# avoccado-avr-pcb-kane-a1.net
KiCad netlist of a schematic drawn in EAGLE
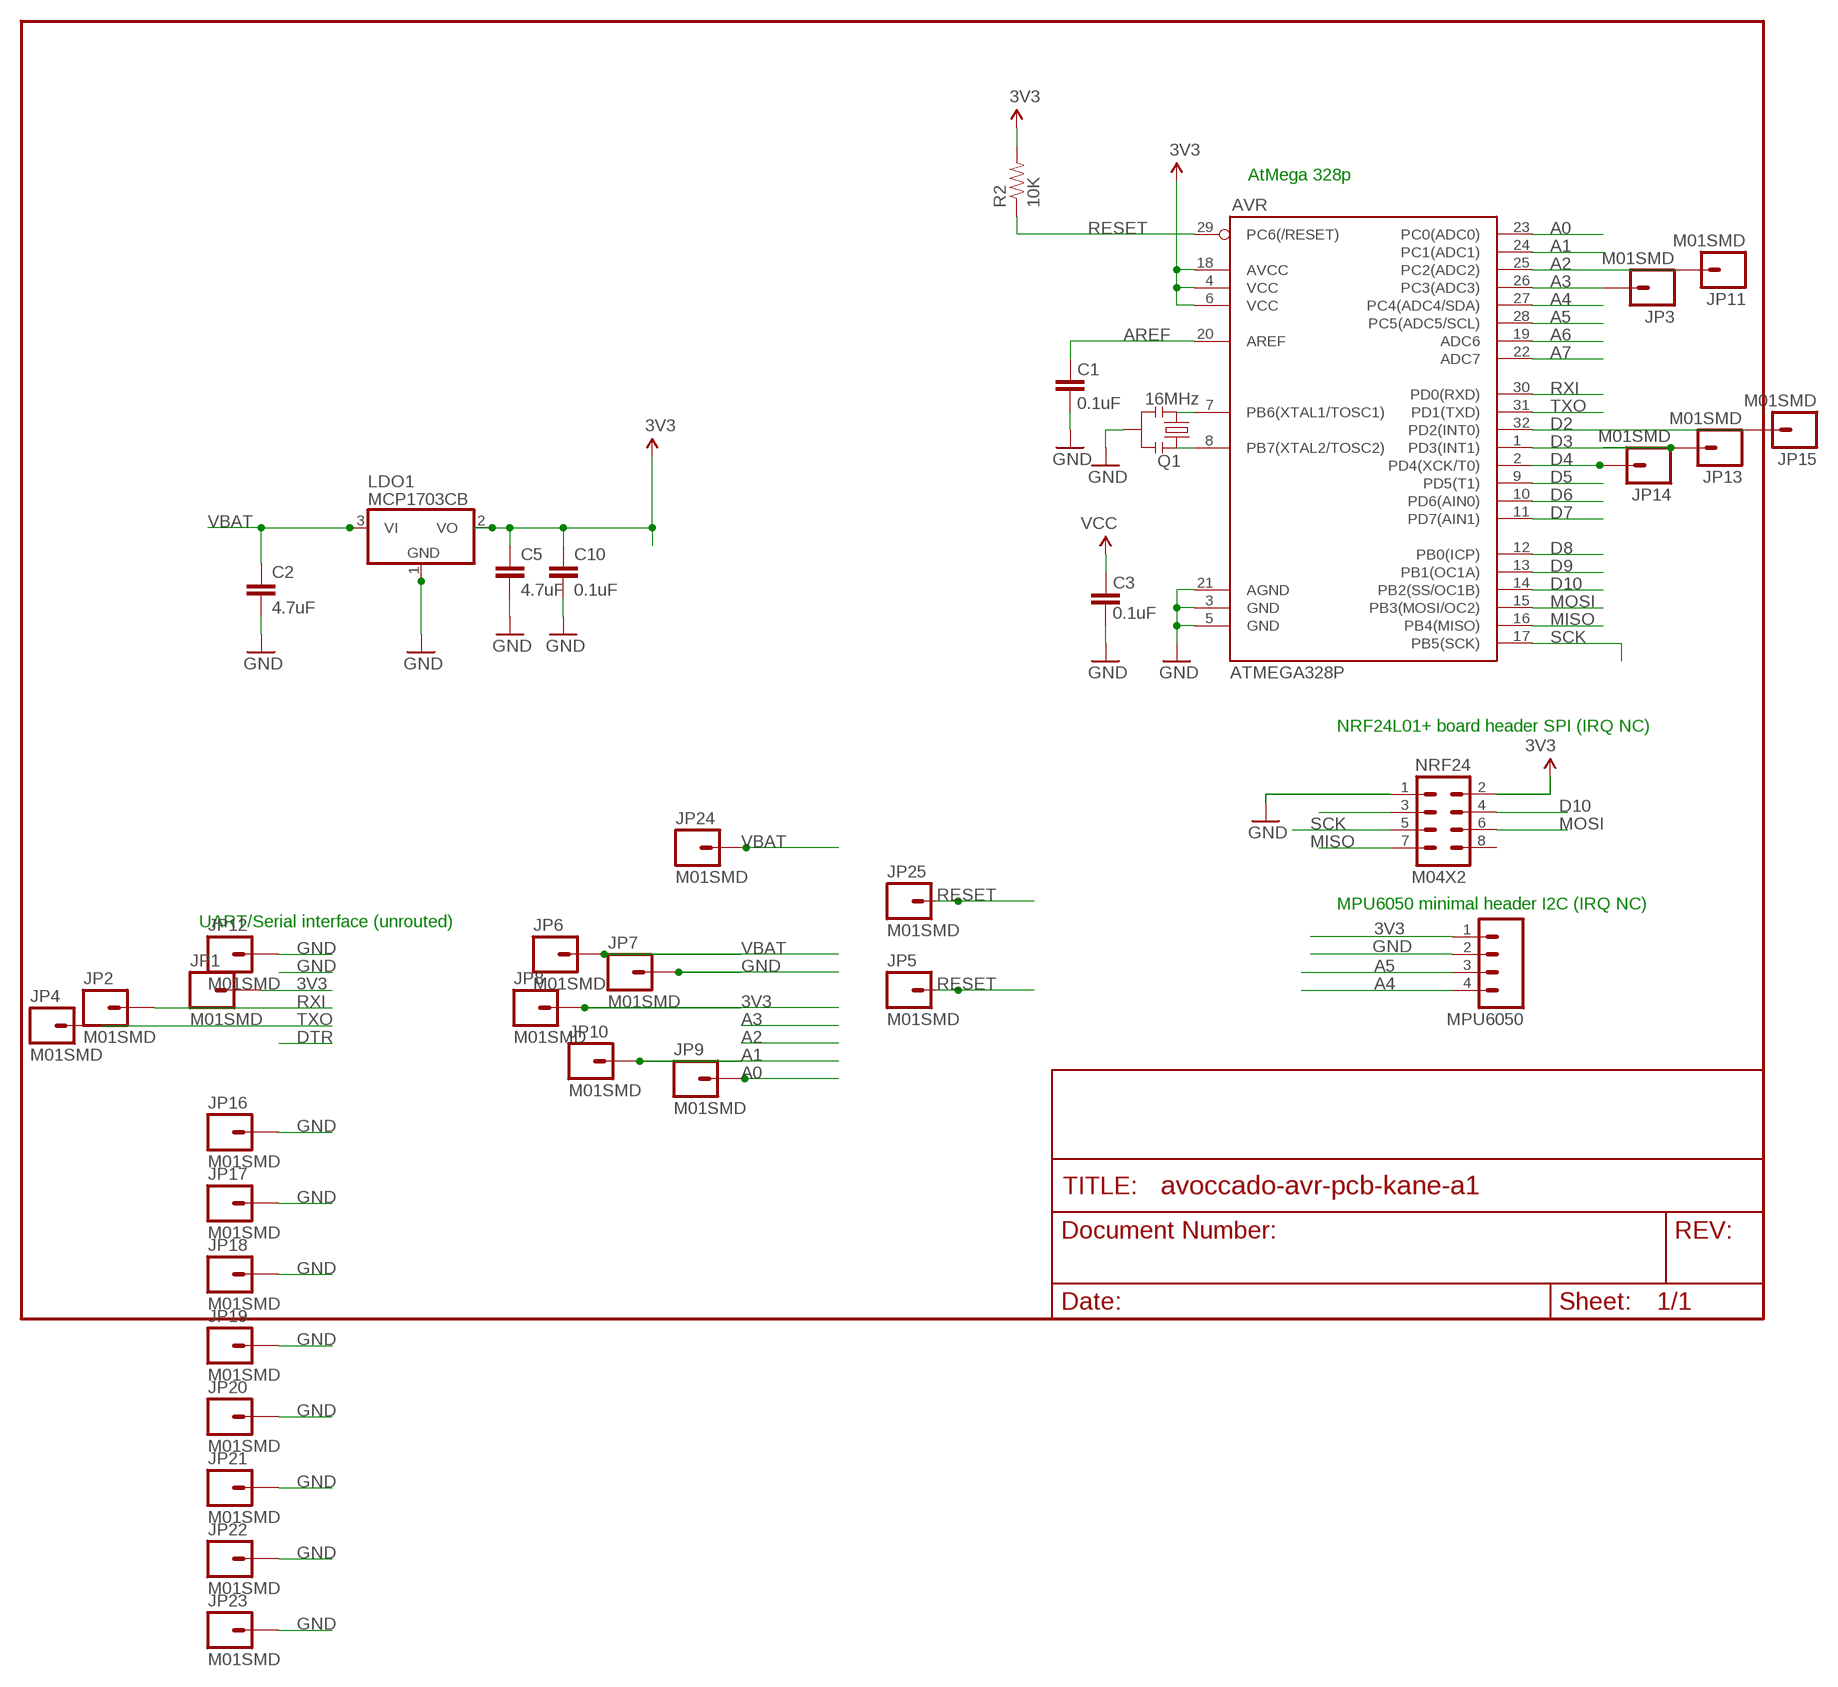
[diagram p0: schematic, sheet 1]

(export (version "E")
  (design (tool "Eeschema 10.0.6"))
  (components
    (comp (ref "AVR")
      (value "ATMEGA328P")
      (footprint "eagle-import:TQFP32-08")
      (libsource (lib "eagle-import") (part "ATMEGA328_SMT"))
    )
    (comp (ref "C1")
      (value "0.1uF")
      (footprint "eagle-import:C0402")
      (libsource (lib "eagle-import") (part "CAP0402"))
    )
    (comp (ref "C2")
      (value "4.7uF")
      (footprint "eagle-import:0603-CAP")
      (libsource (lib "eagle-import") (part "4.7UF-6.3V-10%(0603)0603"))
    )
    (comp (ref "C3")
      (value "0.1uF")
      (footprint "eagle-import:C0402")
      (libsource (lib "eagle-import") (part "CAP0402"))
    )
    (comp (ref "C5")
      (value "4.7uF")
      (footprint "eagle-import:0603-CAP")
      (libsource (lib "eagle-import") (part "4.7UF-6.3V-10%(0603)0603"))
    )
    (comp (ref "C10")
      (value "0.1uF")
      (footprint "eagle-import:C0402")
      (libsource (lib "eagle-import") (part "CAP0402"))
    )
    (comp (ref "JP1")
      (value "M01SMD")
      (footprint "eagle-import:LUXEON-PAD")
      (libsource (lib "eagle-import") (part "M01SMD"))
    )
    (comp (ref "JP2")
      (value "M01SMD")
      (footprint "eagle-import:LUXEON-PAD")
      (libsource (lib "eagle-import") (part "M01SMD"))
    )
    (comp (ref "JP3")
      (value "M01SMD")
      (footprint "eagle-import:LUXEON-PAD")
      (libsource (lib "eagle-import") (part "M01SMD"))
    )
    (comp (ref "JP4")
      (value "M01SMD")
      (footprint "eagle-import:LUXEON-PAD")
      (libsource (lib "eagle-import") (part "M01SMD"))
    )
    (comp (ref "JP5")
      (value "M01SMD")
      (footprint "eagle-import:LUXEON-PAD")
      (libsource (lib "eagle-import") (part "M01SMD"))
    )
    (comp (ref "JP6")
      (value "M01SMD")
      (footprint "eagle-import:LUXEON-PAD")
      (libsource (lib "eagle-import") (part "M01SMD"))
    )
    (comp (ref "JP7")
      (value "M01SMD")
      (footprint "eagle-import:LUXEON-PAD")
      (libsource (lib "eagle-import") (part "M01SMD"))
    )
    (comp (ref "JP8")
      (value "M01SMD")
      (footprint "eagle-import:LUXEON-PAD")
      (libsource (lib "eagle-import") (part "M01SMD"))
    )
    (comp (ref "JP9")
      (value "M01SMD")
      (footprint "eagle-import:LUXEON-PAD")
      (libsource (lib "eagle-import") (part "M01SMD"))
    )
    (comp (ref "JP10")
      (value "M01SMD")
      (footprint "eagle-import:LUXEON-PAD")
      (libsource (lib "eagle-import") (part "M01SMD"))
    )
    (comp (ref "JP11")
      (value "M01SMD")
      (footprint "eagle-import:LUXEON-PAD")
      (libsource (lib "eagle-import") (part "M01SMD"))
    )
    (comp (ref "JP12")
      (value "M01SMD")
      (footprint "eagle-import:LUXEON-PAD")
      (libsource (lib "eagle-import") (part "M01SMD"))
    )
    (comp (ref "JP13")
      (value "M01SMD")
      (footprint "eagle-import:LUXEON-PAD")
      (libsource (lib "eagle-import") (part "M01SMD"))
    )
    (comp (ref "JP14")
      (value "M01SMD")
      (footprint "eagle-import:LUXEON-PAD")
      (libsource (lib "eagle-import") (part "M01SMD"))
    )
    (comp (ref "JP15")
      (value "M01SMD")
      (footprint "eagle-import:LUXEON-PAD")
      (libsource (lib "eagle-import") (part "M01SMD"))
    )
    (comp (ref "JP16")
      (value "M01SMD")
      (footprint "eagle-import:LUXEON-PAD")
      (libsource (lib "eagle-import") (part "M01SMD"))
    )
    (comp (ref "JP17")
      (value "M01SMD")
      (footprint "eagle-import:LUXEON-PAD")
      (libsource (lib "eagle-import") (part "M01SMD"))
    )
    (comp (ref "JP18")
      (value "M01SMD")
      (footprint "eagle-import:LUXEON-PAD")
      (libsource (lib "eagle-import") (part "M01SMD"))
    )
    (comp (ref "JP19")
      (value "M01SMD")
      (footprint "eagle-import:LUXEON-PAD")
      (libsource (lib "eagle-import") (part "M01SMD"))
    )
    (comp (ref "JP20")
      (value "M01SMD")
      (footprint "eagle-import:LUXEON-PAD")
      (libsource (lib "eagle-import") (part "M01SMD"))
    )
    (comp (ref "JP21")
      (value "M01SMD")
      (footprint "eagle-import:LUXEON-PAD")
      (libsource (lib "eagle-import") (part "M01SMD"))
    )
    (comp (ref "JP22")
      (value "M01SMD")
      (footprint "eagle-import:LUXEON-PAD")
      (libsource (lib "eagle-import") (part "M01SMD"))
    )
    (comp (ref "JP23")
      (value "M01SMD")
      (footprint "eagle-import:LUXEON-PAD")
      (libsource (lib "eagle-import") (part "M01SMD"))
    )
    (comp (ref "JP24")
      (value "M01SMD")
      (footprint "eagle-import:LUXEON-PAD")
      (libsource (lib "eagle-import") (part "M01SMD"))
    )
    (comp (ref "JP25")
      (value "M01SMD")
      (footprint "eagle-import:LUXEON-PAD")
      (libsource (lib "eagle-import") (part "M01SMD"))
    )
    (comp (ref "LDO1")
      (value "MCP1703CB")
      (footprint "eagle-import:SOT23")
      (libsource (lib "eagle-import") (part "MCP1703CB"))
    )
    (comp (ref "MPU6050")
      (value "M041X04_NO_SILK")
      (footprint "eagle-import:1X04_NO_SILK")
      (libsource (lib "eagle-import") (part "M041X04_NO_SILK"))
    )
    (comp (ref "NRF24")
      (value "M04X2")
      (footprint "eagle-import:2X4")
      (libsource (lib "eagle-import") (part "M04X2"))
    )
    (comp (ref "Q1")
      (value "16MHz")
      (footprint "eagle-import:RESONATOR-SMD")
      (libsource (lib "eagle-import") (part "RESONATORSMD"))
    )
    (comp (ref "R2")
      (value "10K")
      (footprint "eagle-import:0603-RES")
      (libsource (lib "eagle-import") (part "RESISTOR0603"))
    )
  )
  (nets
    (net (code "1") (name "/A0") (class "Default")
      (node (ref "AVR") (pin "23") (pinfunction "PC0(ADC0)_23") (pintype "bidirectional"))
      (node (ref "JP9") (pin "P$1") (pinfunction "1_P$1") (pintype "passive"))
    )
    (net (code "2") (name "/A1") (class "Default")
      (node (ref "AVR") (pin "24") (pinfunction "PC1(ADC1)_24") (pintype "bidirectional"))
      (node (ref "JP10") (pin "P$1") (pinfunction "1_P$1") (pintype "passive"))
    )
    (net (code "3") (name "/A2") (class "Default")
      (node (ref "AVR") (pin "25") (pinfunction "PC2(ADC2)_25") (pintype "bidirectional"))
      (node (ref "JP11") (pin "P$1") (pinfunction "1_P$1") (pintype "passive"))
    )
    (net (code "4") (name "/A3") (class "Default")
      (node (ref "AVR") (pin "26") (pinfunction "PC3(ADC3)_26") (pintype "bidirectional"))
      (node (ref "JP3") (pin "P$1") (pinfunction "1_P$1") (pintype "passive"))
    )
    (net (code "5") (name "/A4") (class "Default")
      (node (ref "AVR") (pin "27") (pinfunction "PC4(ADC4/SDA)_27") (pintype "bidirectional"))
      (node (ref "MPU6050") (pin "4") (pinfunction "4_4") (pintype "passive"))
    )
    (net (code "6") (name "/A5") (class "Default")
      (node (ref "AVR") (pin "28") (pinfunction "PC5(ADC5/SCL)_28") (pintype "bidirectional"))
      (node (ref "MPU6050") (pin "3") (pinfunction "3_3") (pintype "passive"))
    )
    (net (code "7") (name "/A6") (class "Default")
      (node (ref "AVR") (pin "19") (pinfunction "ADC6_19") (pintype "bidirectional"))
    )
    (net (code "8") (name "/A7") (class "Default")
      (node (ref "AVR") (pin "22") (pinfunction "ADC7_22") (pintype "bidirectional"))
    )
    (net (code "9") (name "/AREF") (class "Default")
      (node (ref "AVR") (pin "20") (pinfunction "AREF_20") (pintype "bidirectional"))
      (node (ref "C1") (pin "2") (pinfunction "2_2") (pintype "passive"))
    )
    (net (code "10") (name "/D2") (class "Default")
      (node (ref "AVR") (pin "32") (pinfunction "PD2(INT0)_32") (pintype "bidirectional"))
      (node (ref "JP15") (pin "P$1") (pinfunction "1_P$1") (pintype "passive"))
    )
    (net (code "11") (name "/D3") (class "Default")
      (node (ref "AVR") (pin "1") (pinfunction "PD3(INT1)_1") (pintype "bidirectional"))
      (node (ref "JP13") (pin "P$1") (pinfunction "1_P$1") (pintype "passive"))
    )
    (net (code "12") (name "/D4") (class "Default")
      (node (ref "AVR") (pin "2") (pinfunction "PD4(XCK/T0)_2") (pintype "bidirectional"))
      (node (ref "JP14") (pin "P$1") (pinfunction "1_P$1") (pintype "passive"))
    )
    (net (code "13") (name "/D5") (class "Default")
      (node (ref "AVR") (pin "9") (pinfunction "PD5(T1)_9") (pintype "bidirectional"))
    )
    (net (code "14") (name "/D6") (class "Default")
      (node (ref "AVR") (pin "10") (pinfunction "PD6(AIN0)_10") (pintype "bidirectional"))
    )
    (net (code "15") (name "/D7") (class "Default")
      (node (ref "AVR") (pin "11") (pinfunction "PD7(AIN1)_11") (pintype "bidirectional"))
    )
    (net (code "16") (name "/D8") (class "Default")
      (node (ref "AVR") (pin "12") (pinfunction "PB0(ICP)_12") (pintype "bidirectional"))
    )
    (net (code "17") (name "/D9") (class "Default")
      (node (ref "AVR") (pin "13") (pinfunction "PB1(OC1A)_13") (pintype "bidirectional"))
      (node (ref "NRF24") (pin "3") (pinfunction "3_3") (pintype "passive"))
    )
    (net (code "18") (name "/D10") (class "Default")
      (node (ref "AVR") (pin "14") (pinfunction "PB2(SS/OC1B)_14") (pintype "bidirectional"))
      (node (ref "NRF24") (pin "4") (pinfunction "4_4") (pintype "passive"))
    )
    (net (code "20") (name "/MISO") (class "Default")
      (node (ref "AVR") (pin "16") (pinfunction "PB4(MISO)_16") (pintype "bidirectional"))
      (node (ref "NRF24") (pin "7") (pinfunction "7_7") (pintype "passive"))
    )
    (net (code "21") (name "/MOSI") (class "Default")
      (node (ref "AVR") (pin "15") (pinfunction "PB3(MOSI/OC2)_15") (pintype "bidirectional"))
      (node (ref "NRF24") (pin "6") (pinfunction "6_6") (pintype "passive"))
    )
    (net (code "22") (name "/RESET") (class "Default")
      (node (ref "AVR") (pin "29") (pinfunction "PC6(/RESET)_29") (pintype "bidirectional"))
      (node (ref "JP25") (pin "P$1") (pinfunction "1_P$1") (pintype "passive"))
      (node (ref "JP5") (pin "P$1") (pinfunction "1_P$1") (pintype "passive"))
      (node (ref "R2") (pin "1") (pinfunction "1_1") (pintype "passive"))
    )
    (net (code "23") (name "/RXI") (class "Default")
      (node (ref "AVR") (pin "30") (pinfunction "PD0(RXD)_30") (pintype "bidirectional"))
      (node (ref "JP2") (pin "P$1") (pinfunction "1_P$1") (pintype "passive"))
    )
    (net (code "24") (name "/SCK") (class "Default")
      (node (ref "AVR") (pin "17") (pinfunction "PB5(SCK)_17") (pintype "bidirectional"))
      (node (ref "NRF24") (pin "5") (pinfunction "5_5") (pintype "passive"))
    )
    (net (code "25") (name "/TXO") (class "Default")
      (node (ref "AVR") (pin "31") (pinfunction "PD1(TXD)_31") (pintype "bidirectional"))
      (node (ref "JP4") (pin "P$1") (pinfunction "1_P$1") (pintype "passive"))
    )
    (net (code "26") (name "/VBAT") (class "Default")
      (node (ref "C2") (pin "1") (pinfunction "1_1") (pintype "passive"))
      (node (ref "JP24") (pin "P$1") (pinfunction "1_P$1") (pintype "passive"))
      (node (ref "JP6") (pin "P$1") (pinfunction "1_P$1") (pintype "passive"))
      (node (ref "LDO1") (pin "3") (pinfunction "VI_3") (pintype "input"))
    )
    (net (code "27") (name "3V3") (class "Default")
      (node (ref "AVR") (pin "18") (pinfunction "AVCC_18") (pintype "bidirectional"))
      (node (ref "AVR") (pin "4") (pinfunction "VCC_4") (pintype "bidirectional"))
      (node (ref "AVR") (pin "6") (pinfunction "VCC_6") (pintype "bidirectional"))
      (node (ref "C10") (pin "1") (pinfunction "1_1") (pintype "passive"))
      (node (ref "C3") (pin "2") (pinfunction "2_2") (pintype "passive"))
      (node (ref "C5") (pin "1") (pinfunction "1_1") (pintype "passive"))
      (node (ref "JP1") (pin "P$1") (pinfunction "1_P$1") (pintype "passive"))
      (node (ref "JP8") (pin "P$1") (pinfunction "1_P$1") (pintype "passive"))
      (node (ref "LDO1") (pin "2") (pinfunction "VO_2") (pintype "passive"))
      (node (ref "MPU6050") (pin "1") (pinfunction "1_1") (pintype "passive"))
      (node (ref "NRF24") (pin "2") (pinfunction "2_2") (pintype "passive"))
      (node (ref "R2") (pin "2") (pinfunction "2_2") (pintype "passive"))
    )
    (net (code "28") (name "GND") (class "Default")
      (node (ref "AVR") (pin "21") (pinfunction "AGND_21") (pintype "bidirectional"))
      (node (ref "AVR") (pin "3") (pinfunction "GND_3") (pintype "bidirectional"))
      (node (ref "AVR") (pin "5") (pinfunction "GND_5") (pintype "bidirectional"))
      (node (ref "C1") (pin "1") (pinfunction "1_1") (pintype "passive"))
      (node (ref "C10") (pin "2") (pinfunction "2_2") (pintype "passive"))
      (node (ref "C2") (pin "2") (pinfunction "2_2") (pintype "passive"))
      (node (ref "C3") (pin "1") (pinfunction "1_1") (pintype "passive"))
      (node (ref "C5") (pin "2") (pinfunction "2_2") (pintype "passive"))
      (node (ref "JP12") (pin "P$1") (pinfunction "1_P$1") (pintype "passive"))
      (node (ref "JP16") (pin "P$1") (pinfunction "1_P$1") (pintype "passive"))
      (node (ref "JP17") (pin "P$1") (pinfunction "1_P$1") (pintype "passive"))
      (node (ref "JP18") (pin "P$1") (pinfunction "1_P$1") (pintype "passive"))
      (node (ref "JP19") (pin "P$1") (pinfunction "1_P$1") (pintype "passive"))
      (node (ref "JP20") (pin "P$1") (pinfunction "1_P$1") (pintype "passive"))
      (node (ref "JP21") (pin "P$1") (pinfunction "1_P$1") (pintype "passive"))
      (node (ref "JP22") (pin "P$1") (pinfunction "1_P$1") (pintype "passive"))
      (node (ref "JP23") (pin "P$1") (pinfunction "1_P$1") (pintype "passive"))
      (node (ref "JP7") (pin "P$1") (pinfunction "1_P$1") (pintype "passive"))
      (node (ref "LDO1") (pin "1") (pinfunction "GND_1") (pintype "passive"))
      (node (ref "MPU6050") (pin "2") (pinfunction "2_2") (pintype "passive"))
      (node (ref "NRF24") (pin "1") (pinfunction "1_1") (pintype "passive"))
      (node (ref "Q1") (pin "2") (pinfunction "2_2") (pintype "passive"))
    )
    (net (code "29") (name "Net-(AVR-PB6(XTAL1{slash}TOSC1))") (class "Default")
      (node (ref "AVR") (pin "7") (pinfunction "PB6(XTAL1/TOSC1)_7") (pintype "bidirectional"))
      (node (ref "Q1") (pin "3") (pinfunction "3_3") (pintype "passive"))
    )
    (net (code "30") (name "Net-(AVR-PB7(XTAL2{slash}TOSC2))") (class "Default")
      (node (ref "AVR") (pin "8") (pinfunction "PB7(XTAL2/TOSC2)_8") (pintype "bidirectional"))
      (node (ref "Q1") (pin "1") (pinfunction "1_1") (pintype "passive"))
    )
    (net (code "31") (name "unconnected-(NRF24-Pad8)") (class "Default")
      (node (ref "NRF24") (pin "8") (pinfunction "8_8") (pintype "passive"))
    )
  )
)
